# MicroController.net
KiCad netlist of a schematic drawn in Altium Designer
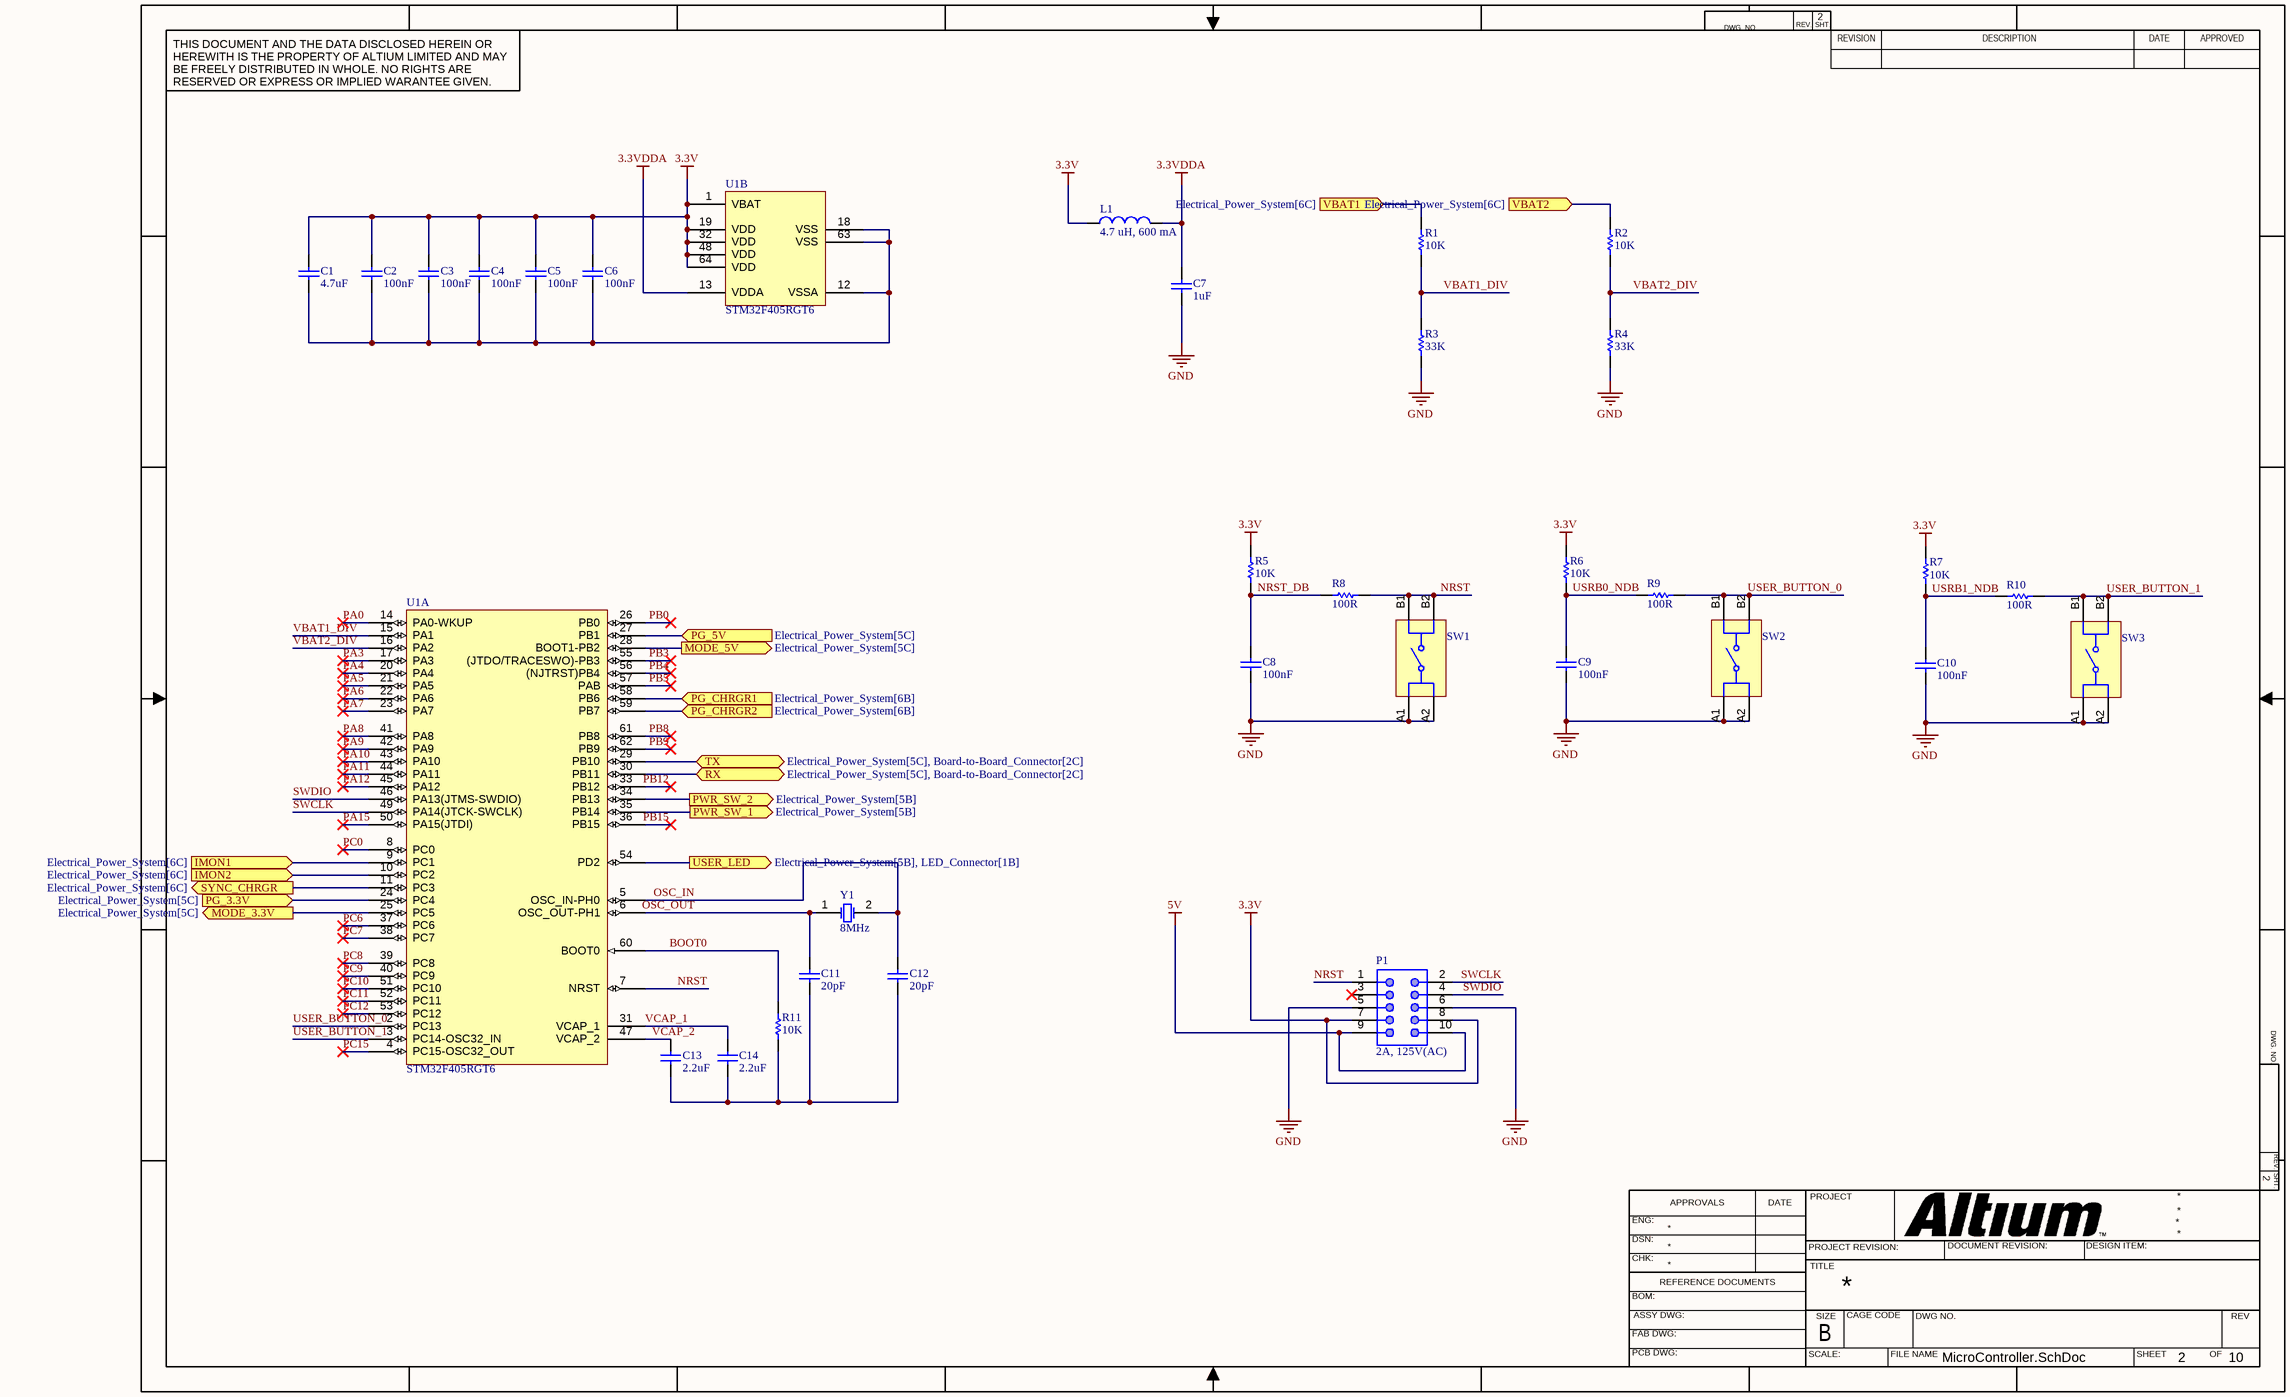
[diagram p0: MicroController.SchDoc]

(export (version "E")
  (design (tool "Eeschema 10.0.6"))
  (components
    (comp (ref "C1")
      (value "4.7uF")
      (footprint "CAP-SM-0603")
      (description "Capacitor")
      (fields (field (name "Comment") "Cap Non-Pol SMD"))
      (libsource (lib "PIF_Library") (part "Cap Non-Pol SMD"))
    )
    (comp (ref "C2")
      (value "100nF")
      (footprint "CAP-SM-0603")
      (description "Capacitor")
      (fields (field (name "Comment") "Cap Non-Pol SMD"))
      (libsource (lib "PIF_Library") (part "Cap Non-Pol SMD"))
    )
    (comp (ref "C3")
      (value "100nF")
      (footprint "CAP-SM-0603")
      (description "Capacitor")
      (fields (field (name "Comment") "Cap Non-Pol SMD"))
      (libsource (lib "PIF_Library") (part "Cap Non-Pol SMD"))
    )
    (comp (ref "C4")
      (value "100nF")
      (footprint "CAP-SM-0603")
      (description "Capacitor")
      (fields (field (name "Comment") "Cap Non-Pol SMD"))
      (libsource (lib "PIF_Library") (part "Cap Non-Pol SMD"))
    )
    (comp (ref "C5")
      (value "100nF")
      (footprint "CAP-SM-0603")
      (description "Capacitor")
      (fields (field (name "Comment") "Cap Non-Pol SMD"))
      (libsource (lib "PIF_Library") (part "Cap Non-Pol SMD"))
    )
    (comp (ref "C6")
      (value "100nF")
      (footprint "CAP-SM-0603")
      (description "Capacitor")
      (fields (field (name "Comment") "Cap Non-Pol SMD"))
      (libsource (lib "PIF_Library") (part "Cap Non-Pol SMD"))
    )
    (comp (ref "C7")
      (value "1uF")
      (footprint "CAP-SM-0603")
      (description "Capacitor")
      (fields (field (name "Comment") "Cap Non-Pol SMD"))
      (libsource (lib "PIF_Library") (part "Cap Non-Pol SMD"))
    )
    (comp (ref "C8")
      (value "100nF")
      (footprint "CAP-SM-0805")
      (description "Capacitor")
      (fields (field (name "Comment") "Cap Non-Pol SMD"))
      (libsource (lib "PIF_Library") (part "Cap Non-Pol SMD"))
    )
    (comp (ref "C9")
      (value "100nF")
      (footprint "CAP-SM-0805")
      (description "Capacitor")
      (fields (field (name "Comment") "Cap Non-Pol SMD"))
      (libsource (lib "PIF_Library") (part "Cap Non-Pol SMD"))
    )
    (comp (ref "C10")
      (value "100nF")
      (footprint "CAP-SM-0805")
      (description "Capacitor")
      (fields (field (name "Comment") "Cap Non-Pol SMD"))
      (libsource (lib "PIF_Library") (part "Cap Non-Pol SMD"))
    )
    (comp (ref "C11")
      (value "20pF")
      (footprint "CAP-SM-0603")
      (description "Capacitor")
      (fields (field (name "Comment") "Cap Non-Pol SMD"))
      (libsource (lib "PIF_Library") (part "Cap Non-Pol SMD"))
    )
    (comp (ref "C12")
      (value "20pF")
      (footprint "CAP-SM-0603")
      (description "Capacitor")
      (fields (field (name "Comment") "Cap Non-Pol SMD"))
      (libsource (lib "PIF_Library") (part "Cap Non-Pol SMD"))
    )
    (comp (ref "C13")
      (value "2.2uF")
      (footprint "CAP-SM-0603")
      (description "Capacitor")
      (fields (field (name "Comment") "Cap Non-Pol SMD"))
      (libsource (lib "PIF_Library") (part "Cap Non-Pol SMD"))
    )
    (comp (ref "C14")
      (value "2.2uF")
      (footprint "CAP-SM-0603")
      (description "Capacitor")
      (fields (field (name "Comment") "Cap Non-Pol SMD"))
      (libsource (lib "PIF_Library") (part "Cap Non-Pol SMD"))
    )
    (comp (ref "L1")
      (value "4.7 uH, 600 mA")
      (footprint "0805")
      (description "Inductor SMD, size 0805, 4.7 uH, 600 mA")
      (fields (field (name "TOLERANCE") "20%") (field (name "MANUFACTURER") "TDK"))
      (libsource (lib "Altium_Inductor") (part "02080547520600"))
    )
    (comp (ref "P1")
      (value "2A, 125V(AC)")
      (footprint "62401021722")
      (description "WR-WTB THT Male Horizontal Shrouded Header with positive locking, Dual Row, pitch 2mm, 10p")
      (fields (field (name "PART NUMBER") "62401021722") (field (name "MANUFACTURER") "Wurth Elektronik"))
      (libsource (lib "Altium_PCB_Connector") (part "62401021722"))
    )
    (comp (ref "R1")
      (value "10K")
      (footprint "RES-SM-0805")
      (description "Resistor")
      (fields (field (name "Comment") "RESISTOR SMD"))
      (libsource (lib "PIF_Library") (part "RESISTOR SMD"))
    )
    (comp (ref "R2")
      (value "10K")
      (footprint "RES-SM-0805")
      (description "Resistor")
      (fields (field (name "Comment") "RESISTOR SMD"))
      (libsource (lib "PIF_Library") (part "RESISTOR SMD"))
    )
    (comp (ref "R3")
      (value "33K")
      (footprint "RES-SM-0805")
      (description "Resistor")
      (fields (field (name "Comment") "RESISTOR SMD"))
      (libsource (lib "PIF_Library") (part "RESISTOR SMD"))
    )
    (comp (ref "R4")
      (value "33K")
      (footprint "RES-SM-0805")
      (description "Resistor")
      (fields (field (name "Comment") "RESISTOR SMD"))
      (libsource (lib "PIF_Library") (part "RESISTOR SMD"))
    )
    (comp (ref "R5")
      (value "10K")
      (footprint "RES-SM-0805")
      (description "Resistor")
      (fields (field (name "Comment") "RESISTOR SMD"))
      (libsource (lib "PIF_Library") (part "RESISTOR SMD"))
    )
    (comp (ref "R6")
      (value "10K")
      (footprint "RES-SM-0805")
      (description "Resistor")
      (fields (field (name "Comment") "RESISTOR SMD"))
      (libsource (lib "PIF_Library") (part "RESISTOR SMD"))
    )
    (comp (ref "R7")
      (value "10K")
      (footprint "RES-SM-0805")
      (description "Resistor")
      (fields (field (name "Comment") "RESISTOR SMD"))
      (libsource (lib "PIF_Library") (part "RESISTOR SMD"))
    )
    (comp (ref "R8")
      (value "100R")
      (footprint "RES-SM-0805")
      (description "Resistor")
      (fields (field (name "Comment") "RESISTOR SMD"))
      (libsource (lib "PIF_Library") (part "RESISTOR SMD"))
    )
    (comp (ref "R9")
      (value "100R")
      (footprint "RES-SM-0805")
      (description "Resistor")
      (fields (field (name "Comment") "RESISTOR SMD"))
      (libsource (lib "PIF_Library") (part "RESISTOR SMD"))
    )
    (comp (ref "R10")
      (value "100R")
      (footprint "RES-SM-0805")
      (description "Resistor")
      (fields (field (name "Comment") "RESISTOR SMD"))
      (libsource (lib "PIF_Library") (part "RESISTOR SMD"))
    )
    (comp (ref "R11")
      (value "10K")
      (footprint "RES-SM-0805")
      (description "Resistor")
      (fields (field (name "Comment") "RESISTOR SMD"))
      (libsource (lib "PIF_Library") (part "RESISTOR SMD"))
    )
    (comp (ref "SW1")
      (value "430152050826")
      (footprint "WS-TASV_L6W6H5_4301x20508x6")
      (description "WS-TASV SMT Tact Switch, L6 x W6 x H5mm, 260g, SPST-NO, 12V, 50mA")
      (fields (field (name "MANUFACTURER") "Wurth Elektronik"))
      (libsource (lib "Altium_Button") (part "430152050826"))
    )
    (comp (ref "SW2")
      (value "430152050826")
      (footprint "WS-TASV_L6W6H5_4301x20508x6")
      (description "WS-TASV SMT Tact Switch, L6 x W6 x H5mm, 260g, SPST-NO, 12V, 50mA")
      (fields (field (name "MANUFACTURER") "Wurth Elektronik"))
      (libsource (lib "Altium_Button") (part "430152050826"))
    )
    (comp (ref "SW3")
      (value "430152050826")
      (footprint "WS-TASV_L6W6H5_4301x20508x6")
      (description "WS-TASV SMT Tact Switch, L6 x W6 x H5mm, 260g, SPST-NO, 12V, 50mA")
      (fields (field (name "MANUFACTURER") "Wurth Elektronik"))
      (libsource (lib "Altium_Button") (part "430152050826"))
    )
    (comp (ref "U1")
      (value "STM32F405RGT6")
      (footprint "STM32F405RGT6")
      (libsource (lib "EPS_Board_Lib") (part "STM32F405RGT6"))
    )
    (comp (ref "Y1")
      (value "8MHz")
      (footprint "WE-XTAL_HC49/4HSMX")
      (description "WE-XTAL Quartz Crystal, SMT, HC49/4HSMX, 8MHz, +/-30ppm")
      (fields
        (field (name "MANUFACTURER PART NUMBER") "830003151")
        (field (name "MANUFACTURER") "Wurth Elektronik")
      )
      (libsource (lib "Altium_XTAL") (part "071105086016"))
    )
  )
  (nets
    (net (code "1") (name "/BOOT0") (class "Default")
      (node (ref "R11") (pin "2") (pinfunction "2_2") (pintype "passive"))
      (node (ref "U1") (pin "60") (pinfunction "BOOT0_60") (pintype "input"))
    )
    (net (code "2") (name "/IMON1") (class "Default")
      (node (ref "U1") (pin "9") (pinfunction "PC1_9") (pintype "bidirectional"))
    )
    (net (code "3") (name "/IMON2") (class "Default")
      (node (ref "U1") (pin "10") (pinfunction "PC2_10") (pintype "bidirectional"))
    )
    (net (code "4") (name "/MODE_3.3V") (class "Default")
      (node (ref "U1") (pin "25") (pinfunction "PC5_25") (pintype "bidirectional"))
    )
    (net (code "5") (name "/MODE_5V") (class "Default")
      (node (ref "U1") (pin "28") (pinfunction "BOOT1-PB2_28") (pintype "bidirectional"))
    )
    (net (code "6") (name "/NRST") (class "Default")
      (node (ref "P1") (pin "1") (pinfunction "1_1") (pintype "passive"))
      (node (ref "R8") (pin "2") (pinfunction "2_2") (pintype "passive"))
      (node (ref "SW1") (pin "B1") (pinfunction "B1_B1") (pintype "passive"))
      (node (ref "SW1") (pin "B2") (pinfunction "B2_B2") (pintype "passive"))
      (node (ref "U1") (pin "7") (pinfunction "NRST_7") (pintype "bidirectional"))
    )
    (net (code "7") (name "/NRST_DB") (class "Default")
      (node (ref "C8") (pin "2") (pinfunction "2_2") (pintype "passive"))
      (node (ref "R5") (pin "1") (pinfunction "1_1") (pintype "passive"))
      (node (ref "R8") (pin "1") (pinfunction "1_1") (pintype "passive"))
    )
    (net (code "8") (name "/OSC_IN") (class "Default")
      (node (ref "C12") (pin "2") (pinfunction "2_2") (pintype "passive"))
      (node (ref "U1") (pin "5") (pinfunction "OSC_IN-PH0_5") (pintype "bidirectional"))
      (node (ref "Y1") (pin "2") (pinfunction "OSC2_2") (pintype "passive"))
    )
    (net (code "9") (name "/OSC_OUT") (class "Default")
      (node (ref "C11") (pin "2") (pinfunction "2_2") (pintype "passive"))
      (node (ref "U1") (pin "6") (pinfunction "OSC_OUT-PH1_6") (pintype "bidirectional"))
      (node (ref "Y1") (pin "1") (pinfunction "OSC1_1") (pintype "passive"))
    )
    (net (code "10") (name "/PA0") (class "Default")
      (node (ref "U1") (pin "14") (pinfunction "PA0-WKUP_14") (pintype "bidirectional+no_connect"))
    )
    (net (code "11") (name "/PA3") (class "Default")
      (node (ref "U1") (pin "17") (pinfunction "PA3_17") (pintype "bidirectional+no_connect"))
    )
    (net (code "12") (name "/PA4") (class "Default")
      (node (ref "U1") (pin "20") (pinfunction "PA4_20") (pintype "bidirectional+no_connect"))
    )
    (net (code "13") (name "/PA5") (class "Default")
      (node (ref "U1") (pin "21") (pinfunction "PA5_21") (pintype "bidirectional+no_connect"))
    )
    (net (code "14") (name "/PA6") (class "Default")
      (node (ref "U1") (pin "22") (pinfunction "PA6_22") (pintype "bidirectional+no_connect"))
    )
    (net (code "15") (name "/PA7") (class "Default")
      (node (ref "U1") (pin "23") (pinfunction "PA7_23") (pintype "bidirectional+no_connect"))
    )
    (net (code "16") (name "/PA8") (class "Default")
      (node (ref "U1") (pin "41") (pinfunction "PA8_41") (pintype "bidirectional+no_connect"))
    )
    (net (code "17") (name "/PA9") (class "Default")
      (node (ref "U1") (pin "42") (pinfunction "PA9_42") (pintype "bidirectional+no_connect"))
    )
    (net (code "18") (name "/PA10") (class "Default")
      (node (ref "U1") (pin "43") (pinfunction "PA10_43") (pintype "bidirectional+no_connect"))
    )
    (net (code "19") (name "/PA11") (class "Default")
      (node (ref "U1") (pin "44") (pinfunction "PA11_44") (pintype "bidirectional+no_connect"))
    )
    (net (code "20") (name "/PA12") (class "Default")
      (node (ref "U1") (pin "45") (pinfunction "PA12_45") (pintype "bidirectional+no_connect"))
    )
    (net (code "21") (name "/PA15") (class "Default")
      (node (ref "U1") (pin "50") (pinfunction "PA15(JTDI)_50") (pintype "bidirectional+no_connect"))
    )
    (net (code "22") (name "/PB0") (class "Default")
      (node (ref "U1") (pin "26") (pinfunction "PB0_26") (pintype "bidirectional+no_connect"))
    )
    (net (code "23") (name "/PB3") (class "Default")
      (node (ref "U1") (pin "55") (pinfunction "(JTDO/TRACESWO)-PB3_55") (pintype "bidirectional+no_connect"))
    )
    (net (code "24") (name "/PB4") (class "Default")
      (node (ref "U1") (pin "56") (pinfunction "(NJTRST)PB4_56") (pintype "bidirectional+no_connect"))
    )
    (net (code "25") (name "/PB5") (class "Default")
      (node (ref "U1") (pin "57") (pinfunction "PAB_57") (pintype "bidirectional+no_connect"))
    )
    (net (code "26") (name "/PB8") (class "Default")
      (node (ref "U1") (pin "61") (pinfunction "PB8_61") (pintype "bidirectional+no_connect"))
    )
    (net (code "27") (name "/PB9") (class "Default")
      (node (ref "U1") (pin "62") (pinfunction "PB9_62") (pintype "bidirectional+no_connect"))
    )
    (net (code "28") (name "/PB12") (class "Default")
      (node (ref "U1") (pin "33") (pinfunction "PB12_33") (pintype "bidirectional+no_connect"))
    )
    (net (code "29") (name "/PB15") (class "Default")
      (node (ref "U1") (pin "36") (pinfunction "PB15_36") (pintype "bidirectional+no_connect"))
    )
    (net (code "30") (name "/PC0") (class "Default")
      (node (ref "U1") (pin "8") (pinfunction "PC0_8") (pintype "bidirectional+no_connect"))
    )
    (net (code "31") (name "/PC6") (class "Default")
      (node (ref "U1") (pin "37") (pinfunction "PC6_37") (pintype "bidirectional+no_connect"))
    )
    (net (code "32") (name "/PC7") (class "Default")
      (node (ref "U1") (pin "38") (pinfunction "PC7_38") (pintype "bidirectional+no_connect"))
    )
    (net (code "33") (name "/PC8") (class "Default")
      (node (ref "U1") (pin "39") (pinfunction "PC8_39") (pintype "bidirectional+no_connect"))
    )
    (net (code "34") (name "/PC9") (class "Default")
      (node (ref "U1") (pin "40") (pinfunction "PC9_40") (pintype "bidirectional+no_connect"))
    )
    (net (code "35") (name "/PC10") (class "Default")
      (node (ref "U1") (pin "51") (pinfunction "PC10_51") (pintype "bidirectional+no_connect"))
    )
    (net (code "36") (name "/PC11") (class "Default")
      (node (ref "U1") (pin "52") (pinfunction "PC11_52") (pintype "bidirectional+no_connect"))
    )
    (net (code "37") (name "/PC12") (class "Default")
      (node (ref "U1") (pin "53") (pinfunction "PC12_53") (pintype "bidirectional+no_connect"))
    )
    (net (code "38") (name "/PC15") (class "Default")
      (node (ref "U1") (pin "4") (pinfunction "PC15-OSC32_OUT_4") (pintype "bidirectional+no_connect"))
    )
    (net (code "39") (name "/PG_3.3V") (class "Default")
      (node (ref "U1") (pin "24") (pinfunction "PC4_24") (pintype "bidirectional"))
    )
    (net (code "40") (name "/PG_5V") (class "Default")
      (node (ref "U1") (pin "27") (pinfunction "PB1_27") (pintype "bidirectional"))
    )
    (net (code "41") (name "/PG_CHRGR1") (class "Default")
      (node (ref "U1") (pin "58") (pinfunction "PB6_58") (pintype "bidirectional"))
    )
    (net (code "42") (name "/PG_CHRGR2") (class "Default")
      (node (ref "U1") (pin "59") (pinfunction "PB7_59") (pintype "bidirectional"))
    )
    (net (code "43") (name "/PWR_SW_1") (class "Default")
      (node (ref "U1") (pin "35") (pinfunction "PB14_35") (pintype "bidirectional"))
    )
    (net (code "44") (name "/PWR_SW_2") (class "Default")
      (node (ref "U1") (pin "34") (pinfunction "PB13_34") (pintype "bidirectional"))
    )
    (net (code "45") (name "/RX") (class "Default")
      (node (ref "U1") (pin "30") (pinfunction "PB11_30") (pintype "bidirectional"))
    )
    (net (code "46") (name "/SWCLK") (class "Default")
      (node (ref "P1") (pin "2") (pinfunction "2_2") (pintype "passive"))
      (node (ref "U1") (pin "49") (pinfunction "PA14(JTCK-SWCLK)_49") (pintype "bidirectional"))
    )
    (net (code "47") (name "/SWDIO") (class "Default")
      (node (ref "P1") (pin "4") (pinfunction "4_4") (pintype "passive"))
      (node (ref "U1") (pin "46") (pinfunction "PA13(JTMS-SWDIO)_46") (pintype "bidirectional"))
    )
    (net (code "48") (name "/SYNC_CHRGR") (class "Default")
      (node (ref "U1") (pin "11") (pinfunction "PC3_11") (pintype "bidirectional"))
    )
    (net (code "49") (name "/TX") (class "Default")
      (node (ref "U1") (pin "29") (pinfunction "PB10_29") (pintype "bidirectional"))
    )
    (net (code "50") (name "/USER_BUTTON_0") (class "Default")
      (node (ref "R9") (pin "2") (pinfunction "2_2") (pintype "passive"))
      (node (ref "SW2") (pin "B1") (pinfunction "B1_B1") (pintype "passive"))
      (node (ref "SW2") (pin "B2") (pinfunction "B2_B2") (pintype "passive"))
      (node (ref "U1") (pin "2") (pinfunction "PC13_2") (pintype "bidirectional"))
    )
    (net (code "51") (name "/USER_BUTTON_1") (class "Default")
      (node (ref "R10") (pin "2") (pinfunction "2_2") (pintype "passive"))
      (node (ref "SW3") (pin "B1") (pinfunction "B1_B1") (pintype "passive"))
      (node (ref "SW3") (pin "B2") (pinfunction "B2_B2") (pintype "passive"))
      (node (ref "U1") (pin "3") (pinfunction "PC14-OSC32_IN_3") (pintype "bidirectional"))
    )
    (net (code "52") (name "/USER_LED") (class "Default")
      (node (ref "U1") (pin "54") (pinfunction "PD2_54") (pintype "bidirectional"))
    )
    (net (code "53") (name "/USRB0_NDB") (class "Default")
      (node (ref "C9") (pin "2") (pinfunction "2_2") (pintype "passive"))
      (node (ref "R6") (pin "1") (pinfunction "1_1") (pintype "passive"))
      (node (ref "R9") (pin "1") (pinfunction "1_1") (pintype "passive"))
    )
    (net (code "54") (name "/USRB1_NDB") (class "Default")
      (node (ref "C10") (pin "2") (pinfunction "2_2") (pintype "passive"))
      (node (ref "R10") (pin "1") (pinfunction "1_1") (pintype "passive"))
      (node (ref "R7") (pin "1") (pinfunction "1_1") (pintype "passive"))
    )
    (net (code "55") (name "/VBAT1") (class "Default")
      (node (ref "R1") (pin "2") (pinfunction "2_2") (pintype "passive"))
    )
    (net (code "56") (name "/VBAT1_DIV") (class "Default")
      (node (ref "R1") (pin "1") (pinfunction "1_1") (pintype "passive"))
      (node (ref "R3") (pin "2") (pinfunction "2_2") (pintype "passive"))
      (node (ref "U1") (pin "15") (pinfunction "PA1_15") (pintype "bidirectional"))
    )
    (net (code "57") (name "/VBAT2") (class "Default")
      (node (ref "R2") (pin "2") (pinfunction "2_2") (pintype "passive"))
    )
    (net (code "58") (name "/VBAT2_DIV") (class "Default")
      (node (ref "R2") (pin "1") (pinfunction "1_1") (pintype "passive"))
      (node (ref "R4") (pin "2") (pinfunction "2_2") (pintype "passive"))
      (node (ref "U1") (pin "16") (pinfunction "PA2_16") (pintype "bidirectional"))
    )
    (net (code "59") (name "/VCAP_1") (class "Default")
      (node (ref "C14") (pin "2") (pinfunction "2_2") (pintype "passive"))
      (node (ref "U1") (pin "31") (pinfunction "VCAP_1_31") (pintype "passive"))
    )
    (net (code "60") (name "/VCAP_2") (class "Default")
      (node (ref "C13") (pin "2") (pinfunction "2_2") (pintype "passive"))
      (node (ref "U1") (pin "47") (pinfunction "VCAP_2_47") (pintype "passive"))
    )
    (net (code "61") (name "3.3V") (class "Default")
      (node (ref "C1") (pin "2") (pinfunction "2_2") (pintype "passive"))
      (node (ref "C2") (pin "2") (pinfunction "2_2") (pintype "passive"))
      (node (ref "C3") (pin "2") (pinfunction "2_2") (pintype "passive"))
      (node (ref "C4") (pin "2") (pinfunction "2_2") (pintype "passive"))
      (node (ref "C5") (pin "2") (pinfunction "2_2") (pintype "passive"))
      (node (ref "C6") (pin "2") (pinfunction "2_2") (pintype "passive"))
      (node (ref "L1") (pin "1") (pinfunction "1_1") (pintype "passive"))
      (node (ref "P1") (pin "7") (pinfunction "7_7") (pintype "passive"))
      (node (ref "P1") (pin "8") (pinfunction "8_8") (pintype "passive"))
      (node (ref "R5") (pin "2") (pinfunction "2_2") (pintype "passive"))
      (node (ref "R6") (pin "2") (pinfunction "2_2") (pintype "passive"))
      (node (ref "R7") (pin "2") (pinfunction "2_2") (pintype "passive"))
      (node (ref "U1") (pin "1") (pinfunction "VBAT_1") (pintype "passive"))
      (node (ref "U1") (pin "19") (pinfunction "VDD_19") (pintype "passive"))
      (node (ref "U1") (pin "32") (pinfunction "VDD_32") (pintype "passive"))
      (node (ref "U1") (pin "48") (pinfunction "VDD_48") (pintype "passive"))
      (node (ref "U1") (pin "64") (pinfunction "VDD_64") (pintype "passive"))
    )
    (net (code "62") (name "3.3VDDA") (class "Default")
      (node (ref "C7") (pin "2") (pinfunction "2_2") (pintype "passive"))
      (node (ref "L1") (pin "2") (pinfunction "2_2") (pintype "passive"))
      (node (ref "U1") (pin "13") (pinfunction "VDDA_13") (pintype "passive"))
    )
    (net (code "63") (name "5V") (class "Default")
      (node (ref "P1") (pin "10") (pinfunction "10_10") (pintype "passive"))
      (node (ref "P1") (pin "9") (pinfunction "9_9") (pintype "passive"))
    )
    (net (code "64") (name "GND") (class "Default")
      (node (ref "C10") (pin "1") (pinfunction "1_1") (pintype "passive"))
      (node (ref "C7") (pin "1") (pinfunction "1_1") (pintype "passive"))
      (node (ref "C8") (pin "1") (pinfunction "1_1") (pintype "passive"))
      (node (ref "C9") (pin "1") (pinfunction "1_1") (pintype "passive"))
      (node (ref "P1") (pin "5") (pinfunction "5_5") (pintype "passive"))
      (node (ref "P1") (pin "6") (pinfunction "6_6") (pintype "passive"))
      (node (ref "R3") (pin "1") (pinfunction "1_1") (pintype "passive"))
      (node (ref "R4") (pin "1") (pinfunction "1_1") (pintype "passive"))
      (node (ref "SW1") (pin "A1") (pinfunction "A1_A1") (pintype "passive"))
      (node (ref "SW1") (pin "A2") (pinfunction "A2_A2") (pintype "passive"))
      (node (ref "SW2") (pin "A1") (pinfunction "A1_A1") (pintype "passive"))
      (node (ref "SW2") (pin "A2") (pinfunction "A2_A2") (pintype "passive"))
      (node (ref "SW3") (pin "A1") (pinfunction "A1_A1") (pintype "passive"))
      (node (ref "SW3") (pin "A2") (pinfunction "A2_A2") (pintype "passive"))
    )
    (net (code "65") (name "Net-(C11-Pad1)") (class "Default")
      (node (ref "C11") (pin "1") (pinfunction "1_1") (pintype "passive"))
      (node (ref "C12") (pin "1") (pinfunction "1_1") (pintype "passive"))
      (node (ref "C13") (pin "1") (pinfunction "1_1") (pintype "passive"))
      (node (ref "C14") (pin "1") (pinfunction "1_1") (pintype "passive"))
      (node (ref "R11") (pin "1") (pinfunction "1_1") (pintype "passive"))
    )
    (net (code "66") (name "Net-(U1B-VSSA)") (class "Default")
      (node (ref "C1") (pin "1") (pinfunction "1_1") (pintype "passive"))
      (node (ref "C2") (pin "1") (pinfunction "1_1") (pintype "passive"))
      (node (ref "C3") (pin "1") (pinfunction "1_1") (pintype "passive"))
      (node (ref "C4") (pin "1") (pinfunction "1_1") (pintype "passive"))
      (node (ref "C5") (pin "1") (pinfunction "1_1") (pintype "passive"))
      (node (ref "C6") (pin "1") (pinfunction "1_1") (pintype "passive"))
      (node (ref "U1") (pin "12") (pinfunction "VSSA_12") (pintype "passive"))
      (node (ref "U1") (pin "18") (pinfunction "VSS_18") (pintype "passive"))
      (node (ref "U1") (pin "63") (pinfunction "VSS_63") (pintype "passive"))
    )
    (net (code "67") (name "unconnected-(P1-Pad3)") (class "Default")
      (node (ref "P1") (pin "3") (pinfunction "3_3") (pintype "passive+no_connect"))
    )
  )
)
